# CanSwitch.net
KiCad netlist of a schematic drawn in EAGLE
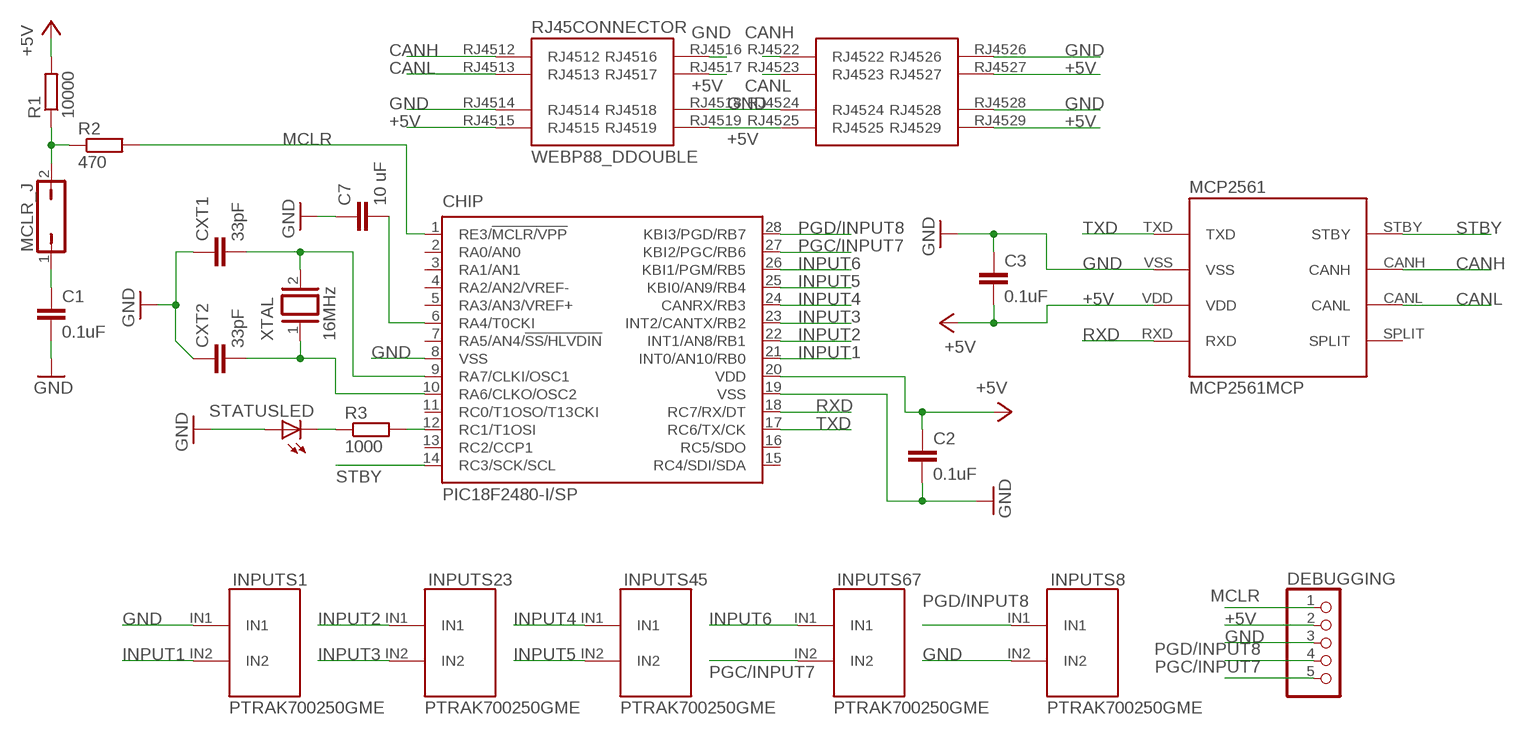
[diagram p0: schematic, sheet 1]

(export (version "E")
  (design (tool "Eeschema 10.0.6"))
  (components
    (comp (ref "C1")
      (value "0.1uF")
      (footprint "eagle-import:C025-025X050")
      (libsource (lib "eagle-import") (part "C-EU025-025X050"))
    )
    (comp (ref "C2")
      (value "0.1uF")
      (footprint "eagle-import:C050-025X075")
      (libsource (lib "eagle-import") (part "C-EU050-025X075"))
    )
    (comp (ref "C3")
      (value "0.1uF")
      (footprint "eagle-import:C050-025X075")
      (libsource (lib "eagle-import") (part "C-EU050-025X075"))
    )
    (comp (ref "C7")
      (value "10 uF")
      (footprint "eagle-import:C050-025X075")
      (libsource (lib "eagle-import") (part "C-EU050-025X075"))
    )
    (comp (ref "CHIP")
      (value "PIC18F2480-I/SP")
      (footprint "eagle-import:DIL28-3")
      (fields (field (name "MF") "MICROCHIP"))
      (libsource (lib "eagle-import") (part "PIC18F280-I/SP4"))
    )
    (comp (ref "CXT1")
      (value "33pF")
      (footprint "eagle-import:C025-030X050")
      (libsource (lib "eagle-import") (part "C-EU025-030X050"))
    )
    (comp (ref "CXT2")
      (value "33pF")
      (footprint "eagle-import:C025-030X050")
      (libsource (lib "eagle-import") (part "C-EU025-030X050"))
    )
    (comp (ref "DEBUGGING")
      (value "PINHD-1X5")
      (footprint "eagle-import:1X05")
      (libsource (lib "eagle-import") (part "PINHD-1X5"))
    )
    (comp (ref "INPUTS1")
      (value "PTRAK700250GME")
      (footprint "eagle-import:PTR_AK700_2_5.0")
      (libsource (lib "eagle-import") (part "PTRAK700250GME"))
    )
    (comp (ref "INPUTS8")
      (value "PTRAK700250GME")
      (footprint "eagle-import:PTR_AK700_2_5.0")
      (libsource (lib "eagle-import") (part "PTRAK700250GME"))
    )
    (comp (ref "INPUTS23")
      (value "PTRAK700250GME")
      (footprint "eagle-import:PTR_AK700_2_5.0")
      (libsource (lib "eagle-import") (part "PTRAK700250GME"))
    )
    (comp (ref "INPUTS45")
      (value "PTRAK700250GME")
      (footprint "eagle-import:PTR_AK700_2_5.0")
      (libsource (lib "eagle-import") (part "PTRAK700250GME"))
    )
    (comp (ref "INPUTS67")
      (value "PTRAK700250GME")
      (footprint "eagle-import:PTR_AK700_2_5.0")
      (libsource (lib "eagle-import") (part "PTRAK700250GME"))
    )
    (comp (ref "MCLR_J")
      (value "JP1Q")
      (footprint "eagle-import:JP1")
      (libsource (lib "eagle-import") (part "JP1Q"))
    )
    (comp (ref "MCP2561")
      (value "MCP2561MCP")
      (footprint "eagle-import:MCP2561_PDIP")
      (libsource (lib "eagle-import") (part "MCP2561MCP"))
    )
    (comp (ref "R1")
      (value "10000")
      (footprint "eagle-import:0207_10")
      (libsource (lib "eagle-import") (part "R-EU_0207/10"))
    )
    (comp (ref "R2")
      (value "470")
      (footprint "eagle-import:0207_10")
      (libsource (lib "eagle-import") (part "R-EU_0207/10"))
    )
    (comp (ref "R3")
      (value "1000")
      (footprint "eagle-import:0207_10")
      (libsource (lib "eagle-import") (part "R-EU_0207/10"))
    )
    (comp (ref "RJ45CONNECTOR")
      (value "WEBP88_DDOUBLE")
      (footprint "eagle-import:WEBP88_RJ45_DOUBLE")
      (libsource (lib "eagle-import") (part "WEBP88_DDOUBLE"))
    )
    (comp (ref "STATUSLED")
      (value "LED5MM")
      (footprint "eagle-import:LED5MM")
      (libsource (lib "eagle-import") (part "LED5MM"))
    )
    (comp (ref "XTAL")
      (value "16MHz")
      (footprint "eagle-import:QS")
      (libsource (lib "eagle-import") (part "XTAL/S"))
    )
  )
  (nets
    (net (code "1") (name "+5V") (class "Default")
      (node (ref "C2") (pin "1") (pinfunction "1_1") (pintype "passive"))
      (node (ref "C3") (pin "2") (pinfunction "2_2") (pintype "passive"))
      (node (ref "CHIP") (pin "20") (pinfunction "VDD_20") (pintype "power_in"))
      (node (ref "DEBUGGING") (pin "2") (pinfunction "2_2") (pintype "passive"))
      (node (ref "MCP2561") (pin "VDD") (pinfunction "VDD_VDD") (pintype "bidirectional"))
      (node (ref "R1") (pin "2") (pinfunction "2_2") (pintype "passive"))
      (node (ref "RJ45CONNECTOR") (pin "RJ4515") (pinfunction "RJ4515_RJ4515") (pintype "bidirectional"))
      (node (ref "RJ45CONNECTOR") (pin "RJ4517") (pinfunction "RJ4517_RJ4517") (pintype "bidirectional"))
      (node (ref "RJ45CONNECTOR") (pin "RJ4519") (pinfunction "RJ4519_RJ4519") (pintype "bidirectional"))
      (node (ref "RJ45CONNECTOR") (pin "RJ4525") (pinfunction "RJ4525_RJ4525") (pintype "bidirectional"))
      (node (ref "RJ45CONNECTOR") (pin "RJ4527") (pinfunction "RJ4527_RJ4527") (pintype "bidirectional"))
      (node (ref "RJ45CONNECTOR") (pin "RJ4529") (pinfunction "RJ4529_RJ4529") (pintype "bidirectional"))
    )
    (net (code "2") (name "/CANH") (class "Default")
      (node (ref "MCP2561") (pin "CANH") (pinfunction "CANH_CANH") (pintype "bidirectional"))
      (node (ref "RJ45CONNECTOR") (pin "RJ4512") (pinfunction "RJ4512_RJ4512") (pintype "bidirectional"))
      (node (ref "RJ45CONNECTOR") (pin "RJ4522") (pinfunction "RJ4522_RJ4522") (pintype "bidirectional"))
    )
    (net (code "3") (name "/CANL") (class "Default")
      (node (ref "MCP2561") (pin "CANL") (pinfunction "CANL_CANL") (pintype "bidirectional"))
      (node (ref "RJ45CONNECTOR") (pin "RJ4513") (pinfunction "RJ4513_RJ4513") (pintype "bidirectional"))
      (node (ref "RJ45CONNECTOR") (pin "RJ4523") (pinfunction "RJ4523_RJ4523") (pintype "bidirectional"))
    )
    (net (code "4") (name "/INPUT1") (class "Default")
      (node (ref "CHIP") (pin "21") (pinfunction "INT0/AN10/RB0_21") (pintype "bidirectional"))
      (node (ref "INPUTS1") (pin "IN2") (pinfunction "IN2_IN2") (pintype "bidirectional"))
    )
    (net (code "5") (name "/INPUT2") (class "Default")
      (node (ref "CHIP") (pin "22") (pinfunction "INT1/AN8/RB1_22") (pintype "bidirectional"))
      (node (ref "INPUTS23") (pin "IN1") (pinfunction "IN1_IN1") (pintype "bidirectional"))
    )
    (net (code "6") (name "/INPUT3") (class "Default")
      (node (ref "CHIP") (pin "23") (pinfunction "INT2/CANTX/RB2_23") (pintype "bidirectional"))
      (node (ref "INPUTS23") (pin "IN2") (pinfunction "IN2_IN2") (pintype "bidirectional"))
    )
    (net (code "7") (name "/INPUT4") (class "Default")
      (node (ref "CHIP") (pin "24") (pinfunction "CANRX/RB3_24") (pintype "bidirectional"))
      (node (ref "INPUTS45") (pin "IN1") (pinfunction "IN1_IN1") (pintype "bidirectional"))
    )
    (net (code "8") (name "/INPUT5") (class "Default")
      (node (ref "CHIP") (pin "25") (pinfunction "KBI0/AN9/RB4_25") (pintype "bidirectional"))
      (node (ref "INPUTS45") (pin "IN2") (pinfunction "IN2_IN2") (pintype "bidirectional"))
    )
    (net (code "9") (name "/INPUT6") (class "Default")
      (node (ref "CHIP") (pin "26") (pinfunction "KBI1/PGM/RB5_26") (pintype "bidirectional"))
      (node (ref "INPUTS67") (pin "IN1") (pinfunction "IN1_IN1") (pintype "bidirectional"))
    )
    (net (code "10") (name "/MCLR") (class "Default")
      (node (ref "CHIP") (pin "1") (pinfunction "RE3/~{MCLR/VPP}_1") (pintype "input"))
      (node (ref "DEBUGGING") (pin "1") (pinfunction "1_1") (pintype "passive"))
      (node (ref "R2") (pin "2") (pinfunction "2_2") (pintype "passive"))
    )
    (net (code "11") (name "/PGC{slash}INPUT7") (class "Default")
      (node (ref "CHIP") (pin "27") (pinfunction "KBI2/PGC/RB6_27") (pintype "bidirectional"))
      (node (ref "DEBUGGING") (pin "5") (pinfunction "5_5") (pintype "passive"))
      (node (ref "INPUTS67") (pin "IN2") (pinfunction "IN2_IN2") (pintype "bidirectional"))
    )
    (net (code "12") (name "/PGD{slash}INPUT8") (class "Default")
      (node (ref "CHIP") (pin "28") (pinfunction "KBI3/PGD/RB7_28") (pintype "bidirectional"))
      (node (ref "DEBUGGING") (pin "4") (pinfunction "4_4") (pintype "passive"))
      (node (ref "INPUTS8") (pin "IN1") (pinfunction "IN1_IN1") (pintype "bidirectional"))
    )
    (net (code "13") (name "/RXD") (class "Default")
      (node (ref "CHIP") (pin "18") (pinfunction "RC7/RX/DT_18") (pintype "bidirectional"))
      (node (ref "MCP2561") (pin "RXD") (pinfunction "RXD_RXD") (pintype "bidirectional"))
    )
    (net (code "14") (name "/STBY") (class "Default")
      (node (ref "CHIP") (pin "14") (pinfunction "RC3/SCK/SCL_14") (pintype "bidirectional"))
      (node (ref "MCP2561") (pin "STBY") (pinfunction "STBY_STBY") (pintype "bidirectional"))
    )
    (net (code "15") (name "/TXD") (class "Default")
      (node (ref "CHIP") (pin "17") (pinfunction "RC6/TX/CK_17") (pintype "bidirectional"))
      (node (ref "MCP2561") (pin "TXD") (pinfunction "TXD_TXD") (pintype "bidirectional"))
    )
    (net (code "16") (name "GND") (class "Default")
      (node (ref "C1") (pin "2") (pinfunction "2_2") (pintype "passive"))
      (node (ref "C2") (pin "2") (pinfunction "2_2") (pintype "passive"))
      (node (ref "C3") (pin "1") (pinfunction "1_1") (pintype "passive"))
      (node (ref "C7") (pin "1") (pinfunction "1_1") (pintype "passive"))
      (node (ref "CHIP") (pin "19") (pinfunction "VSS_19") (pintype "power_in"))
      (node (ref "CHIP") (pin "8") (pinfunction "VSS_8") (pintype "power_in"))
      (node (ref "CXT1") (pin "1") (pinfunction "1_1") (pintype "passive"))
      (node (ref "CXT2") (pin "1") (pinfunction "1_1") (pintype "passive"))
      (node (ref "DEBUGGING") (pin "3") (pinfunction "3_3") (pintype "passive"))
      (node (ref "INPUTS1") (pin "IN1") (pinfunction "IN1_IN1") (pintype "bidirectional"))
      (node (ref "INPUTS8") (pin "IN2") (pinfunction "IN2_IN2") (pintype "bidirectional"))
      (node (ref "MCP2561") (pin "VSS") (pinfunction "VSS_VSS") (pintype "bidirectional"))
      (node (ref "RJ45CONNECTOR") (pin "RJ4514") (pinfunction "RJ4514_RJ4514") (pintype "bidirectional"))
      (node (ref "RJ45CONNECTOR") (pin "RJ4516") (pinfunction "RJ4516_RJ4516") (pintype "bidirectional"))
      (node (ref "RJ45CONNECTOR") (pin "RJ4518") (pinfunction "RJ4518_RJ4518") (pintype "bidirectional"))
      (node (ref "RJ45CONNECTOR") (pin "RJ4524") (pinfunction "RJ4524_RJ4524") (pintype "bidirectional"))
      (node (ref "RJ45CONNECTOR") (pin "RJ4526") (pinfunction "RJ4526_RJ4526") (pintype "bidirectional"))
      (node (ref "RJ45CONNECTOR") (pin "RJ4528") (pinfunction "RJ4528_RJ4528") (pintype "bidirectional"))
      (node (ref "STATUSLED") (pin "A") (pinfunction "A_A") (pintype "passive"))
    )
    (net (code "17") (name "Net-(C1-Pad1)") (class "Default")
      (node (ref "C1") (pin "1") (pinfunction "1_1") (pintype "passive"))
      (node (ref "MCLR_J") (pin "1") (pinfunction "1_1") (pintype "passive"))
    )
    (net (code "18") (name "Net-(CHIP-RA4{slash}T0CKI)") (class "Default")
      (node (ref "C7") (pin "2") (pinfunction "2_2") (pintype "passive"))
      (node (ref "CHIP") (pin "6") (pinfunction "RA4/T0CKI_6") (pintype "bidirectional"))
    )
    (net (code "19") (name "Net-(CHIP-RA6{slash}CLKO{slash}OSC2)") (class "Default")
      (node (ref "CHIP") (pin "10") (pinfunction "RA6/CLKO/OSC2_10") (pintype "output"))
      (node (ref "CXT2") (pin "2") (pinfunction "2_2") (pintype "passive"))
      (node (ref "XTAL") (pin "1") (pinfunction "1_1") (pintype "passive"))
    )
    (net (code "20") (name "Net-(CHIP-RA7{slash}CLKI{slash}OSC1)") (class "Default")
      (node (ref "CHIP") (pin "9") (pinfunction "RA7/CLKI/OSC1_9") (pintype "input"))
      (node (ref "CXT1") (pin "2") (pinfunction "2_2") (pintype "passive"))
      (node (ref "XTAL") (pin "2") (pinfunction "2_2") (pintype "passive"))
    )
    (net (code "21") (name "Net-(CHIP-RC1{slash}T1OSI)") (class "Default")
      (node (ref "CHIP") (pin "12") (pinfunction "RC1/T1OSI_12") (pintype "bidirectional"))
      (node (ref "R3") (pin "2") (pinfunction "2_2") (pintype "passive"))
    )
    (net (code "22") (name "Net-(MCLR_J-Pad2)") (class "Default")
      (node (ref "MCLR_J") (pin "2") (pinfunction "2_2") (pintype "passive"))
      (node (ref "R1") (pin "1") (pinfunction "1_1") (pintype "passive"))
      (node (ref "R2") (pin "1") (pinfunction "1_1") (pintype "passive"))
    )
    (net (code "23") (name "Net-(STATUSLED-C)") (class "Default")
      (node (ref "R3") (pin "1") (pinfunction "1_1") (pintype "passive"))
      (node (ref "STATUSLED") (pin "K") (pinfunction "C_K") (pintype "passive"))
    )
    (net (code "24") (name "unconnected-(CHIP-RA0{slash}AN0-Pad2)") (class "Default")
      (node (ref "CHIP") (pin "2") (pinfunction "RA0/AN0_2") (pintype "bidirectional"))
    )
    (net (code "25") (name "unconnected-(CHIP-RA1{slash}AN1-Pad3)") (class "Default")
      (node (ref "CHIP") (pin "3") (pinfunction "RA1/AN1_3") (pintype "bidirectional"))
    )
    (net (code "26") (name "unconnected-(CHIP-RA2{slash}AN2{slash}VREF--Pad4)") (class "Default")
      (node (ref "CHIP") (pin "4") (pinfunction "RA2/AN2/VREF-_4") (pintype "bidirectional"))
    )
    (net (code "27") (name "unconnected-(CHIP-RA3{slash}AN3{slash}VREF+-Pad5)") (class "Default")
      (node (ref "CHIP") (pin "5") (pinfunction "RA3/AN3/VREF+_5") (pintype "bidirectional"))
    )
    (net (code "28") (name "unconnected-(CHIP-RA5{slash}AN4{slash}~{SS{slash}HLVDIN}-Pad7)") (class "Default")
      (node (ref "CHIP") (pin "7") (pinfunction "RA5/AN4/~{SS/HLVDIN}_7") (pintype "bidirectional"))
    )
    (net (code "29") (name "unconnected-(CHIP-RC0{slash}T1OSO{slash}T13CKI-Pad11)") (class "Default")
      (node (ref "CHIP") (pin "11") (pinfunction "RC0/T1OSO/T13CKI_11") (pintype "bidirectional"))
    )
    (net (code "30") (name "unconnected-(CHIP-RC2{slash}CCP1-Pad13)") (class "Default")
      (node (ref "CHIP") (pin "13") (pinfunction "RC2/CCP1_13") (pintype "bidirectional"))
    )
    (net (code "31") (name "unconnected-(CHIP-RC4{slash}SDI{slash}SDA-Pad15)") (class "Default")
      (node (ref "CHIP") (pin "15") (pinfunction "RC4/SDI/SDA_15") (pintype "bidirectional"))
    )
    (net (code "32") (name "unconnected-(CHIP-RC5{slash}SDO-Pad16)") (class "Default")
      (node (ref "CHIP") (pin "16") (pinfunction "RC5/SDO_16") (pintype "bidirectional"))
    )
    (net (code "33") (name "unconnected-(MCP2561-PadSPLIT)") (class "Default")
      (node (ref "MCP2561") (pin "SPLIT") (pinfunction "SPLIT_SPLIT") (pintype "bidirectional"))
    )
  )
)
